# HIL_Header.net
KiCad netlist of a schematic drawn in Altium Designer
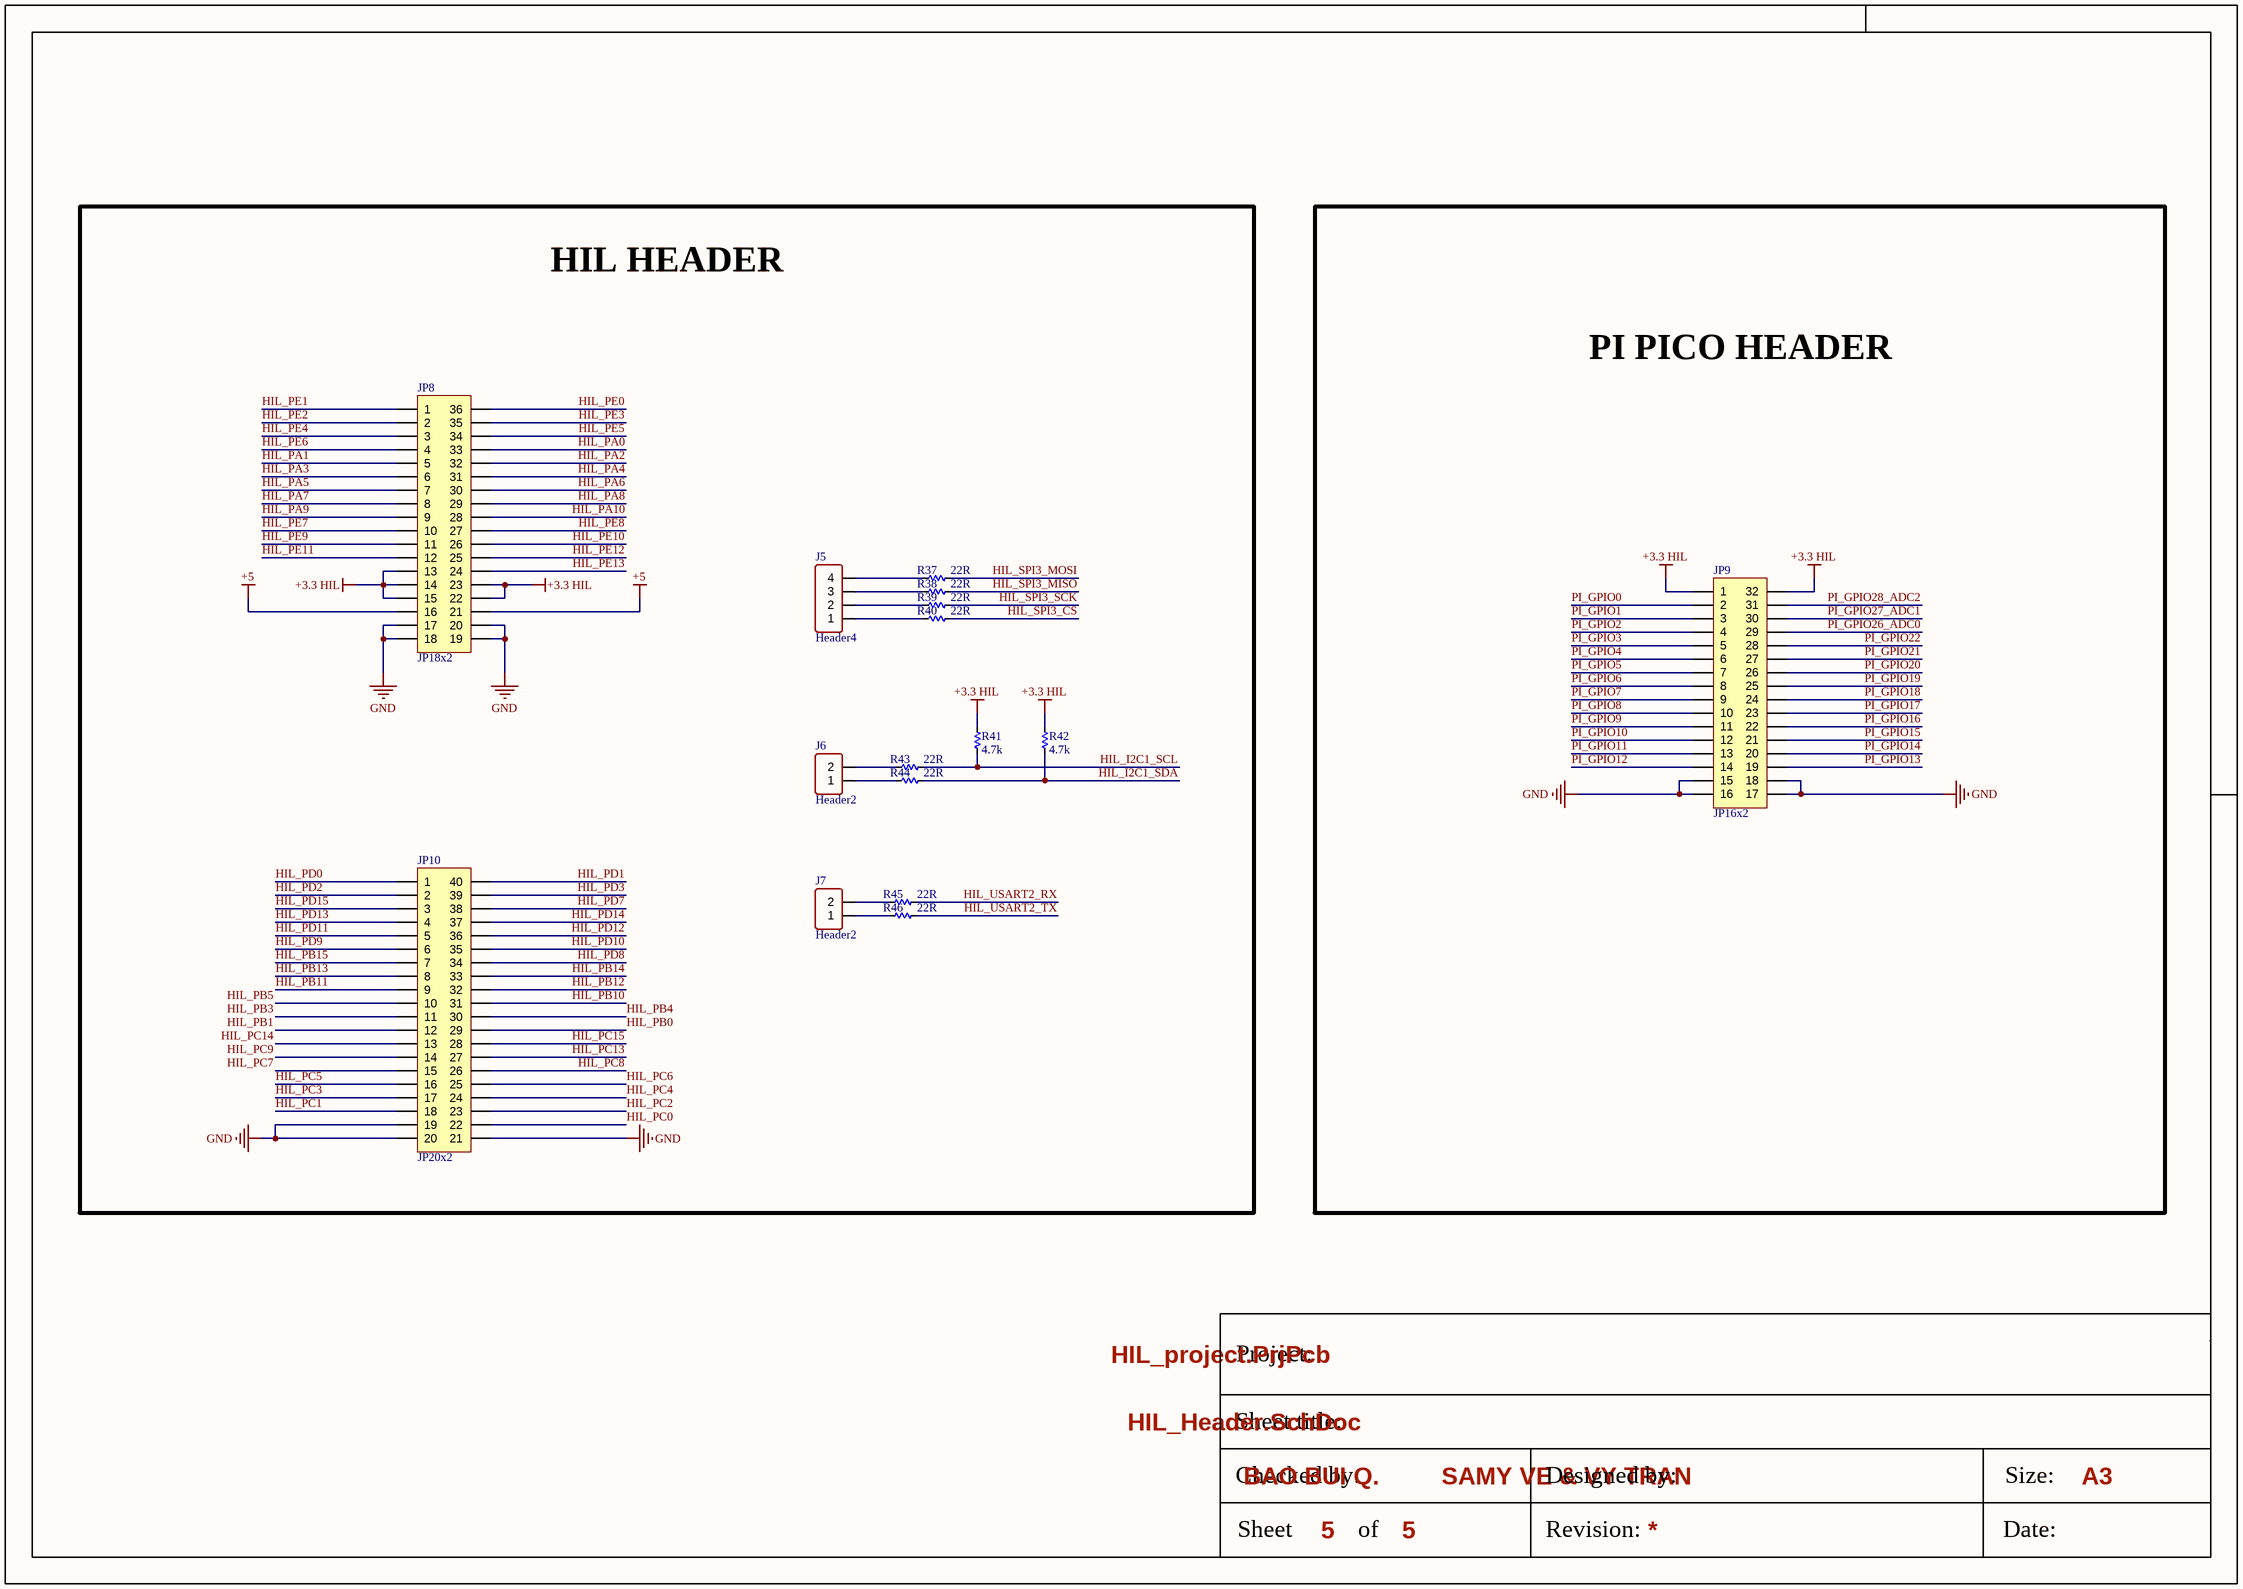
[diagram p0: HIL_Header.SchDoc]

(export (version "E")
  (design (tool "Eeschema 10.0.6"))
  (components
    (comp (ref "J5")
      (value "Header4")
      (footprint "XH2.54-4-DIP")
      (description "Connector 4")
      (fields
        (field (name "MANUFACTURER") "Würth Elektronik eiSos GmbH")
        (field (name "PARTNO") "613002143121")
        (field (name "CREATED BY") "Karrer Zheng")
      )
      (libsource (lib "Library") (part "Header4"))
    )
    (comp (ref "J6")
      (value "Header2")
      (footprint "XH2.54-2-DIP")
      (description "Connector 2")
      (fields
        (field (name "MANUFACTURER") "Würth Elektronik eiSos GmbH")
        (field (name "PARTNO") "613002143121")
        (field (name "CREATED BY") "Karrer Zheng")
      )
      (libsource (lib "Library") (part "Header2"))
    )
    (comp (ref "J7")
      (value "Header2")
      (footprint "XH2.54-2-DIP")
      (description "Connector 2")
      (fields
        (field (name "MANUFACTURER") "Würth Elektronik eiSos GmbH")
        (field (name "PARTNO") "613002143121")
        (field (name "CREATED BY") "Karrer Zheng")
      )
      (libsource (lib "Library") (part "Header2"))
    )
    (comp (ref "JP8")
      (value "JP18x2")
      (footprint "JP18-D2T")
      (description "WR-PHD 2.54 mm Dual Socket Header")
      (fields
        (field (name "MANUFACTURER") "Würth Elektronik eiSos GmbH")
        (field (name "PARTNO") "61303621821")
        (field (name "CREATED BY") "Karrer Zheng")
      )
      (libsource (lib "Library") (part "JP18x2"))
    )
    (comp (ref "JP9")
      (value "JP16x2")
      (footprint "JP16-D2T")
      (description "WR-PHD 2.54 mm Dual Socket Header")
      (fields
        (field (name "MANUFACTURER") "Würth Elektronik eiSos GmbH")
        (field (name "PARTNO") "61303221821")
        (field (name "CREATED BY") "Karrer Zheng")
      )
      (libsource (lib "Library") (part "JP16x2"))
    )
    (comp (ref "JP10")
      (value "JP20x2")
      (footprint "JP20-D2T")
      (description "WR-PHD 2.54 mm Dual Socket Header")
      (fields
        (field (name "MANUFACTURER") "Würth Elektronik eiSos GmbH")
        (field (name "PARTNO") "61304021821")
        (field (name "CREATED BY") "Karrer Zheng")
      )
      (libsource (lib "Library") (part "JP20x2"))
    )
    (comp (ref "R37")
      (value "22R")
      (footprint "RES-SMD-0603")
      (description "Resistor")
      (fields
        (field (name "MANUFACTURER") "Generic Components")
        (field (name "PUBLISHER") "Altium Hobart Technology Centre")
      )
      (libsource (lib "Library") (part "Res-SMD"))
    )
    (comp (ref "R38")
      (value "22R")
      (footprint "RES-SMD-0603")
      (description "Resistor")
      (fields
        (field (name "MANUFACTURER") "Generic Components")
        (field (name "PUBLISHER") "Altium Hobart Technology Centre")
      )
      (libsource (lib "Library") (part "Res-SMD"))
    )
    (comp (ref "R39")
      (value "22R")
      (footprint "RES-SMD-0603")
      (description "Resistor")
      (fields
        (field (name "MANUFACTURER") "Generic Components")
        (field (name "PUBLISHER") "Altium Hobart Technology Centre")
      )
      (libsource (lib "Library") (part "Res-SMD"))
    )
    (comp (ref "R40")
      (value "22R")
      (footprint "RES-SMD-0603")
      (description "Resistor")
      (fields
        (field (name "MANUFACTURER") "Generic Components")
        (field (name "PUBLISHER") "Altium Hobart Technology Centre")
      )
      (libsource (lib "Library") (part "Res-SMD"))
    )
    (comp (ref "R41")
      (value "4.7k")
      (footprint "RES-SMD-0603")
      (description "Resistor")
      (fields
        (field (name "MANUFACTURER") "Generic Components")
        (field (name "PUBLISHER") "Altium Hobart Technology Centre")
      )
      (libsource (lib "Library") (part "Res-SMD"))
    )
    (comp (ref "R42")
      (value "4.7k")
      (footprint "RES-SMD-0603")
      (description "Resistor")
      (fields
        (field (name "MANUFACTURER") "Generic Components")
        (field (name "PUBLISHER") "Altium Hobart Technology Centre")
      )
      (libsource (lib "Library") (part "Res-SMD"))
    )
    (comp (ref "R43")
      (value "22R")
      (footprint "RES-SMD-0603")
      (description "Resistor")
      (fields
        (field (name "MANUFACTURER") "Generic Components")
        (field (name "PUBLISHER") "Altium Hobart Technology Centre")
      )
      (libsource (lib "Library") (part "Res-SMD"))
    )
    (comp (ref "R44")
      (value "22R")
      (footprint "RES-SMD-0603")
      (description "Resistor")
      (fields
        (field (name "MANUFACTURER") "Generic Components")
        (field (name "PUBLISHER") "Altium Hobart Technology Centre")
      )
      (libsource (lib "Library") (part "Res-SMD"))
    )
    (comp (ref "R45")
      (value "22R")
      (footprint "RES-SMD-0603")
      (description "Resistor")
      (fields
        (field (name "MANUFACTURER") "Generic Components")
        (field (name "PUBLISHER") "Altium Hobart Technology Centre")
      )
      (libsource (lib "Library") (part "Res-SMD"))
    )
    (comp (ref "R46")
      (value "22R")
      (footprint "RES-SMD-0603")
      (description "Resistor")
      (fields
        (field (name "MANUFACTURER") "Generic Components")
        (field (name "PUBLISHER") "Altium Hobart Technology Centre")
      )
      (libsource (lib "Library") (part "Res-SMD"))
    )
  )
  (nets
    (net (code "1") (name "+3.3 HIL") (class "Default")
      (node (ref "JP8") (pin "13") (pinfunction "13_13") (pintype "passive"))
      (node (ref "JP8") (pin "14") (pinfunction "14_14") (pintype "passive"))
      (node (ref "JP8") (pin "15") (pinfunction "15_15") (pintype "passive"))
      (node (ref "JP8") (pin "22") (pinfunction "22_22") (pintype "passive"))
      (node (ref "JP8") (pin "23") (pinfunction "23_23") (pintype "passive"))
      (node (ref "JP9") (pin "1") (pinfunction "1_1") (pintype "passive"))
      (node (ref "JP9") (pin "32") (pinfunction "32_32") (pintype "passive"))
      (node (ref "R41") (pin "1") (pinfunction "1_1") (pintype "passive"))
      (node (ref "R42") (pin "1") (pinfunction "1_1") (pintype "passive"))
    )
    (net (code "2") (name "+5") (class "Default")
      (node (ref "JP8") (pin "16") (pinfunction "16_16") (pintype "passive"))
      (node (ref "JP8") (pin "21") (pinfunction "21_21") (pintype "passive"))
    )
    (net (code "3") (name "/HIL_I2C1_SCL") (class "Default")
      (node (ref "R41") (pin "2") (pinfunction "2_2") (pintype "passive"))
      (node (ref "R43") (pin "1") (pinfunction "1_1") (pintype "passive"))
    )
    (net (code "4") (name "/HIL_I2C1_SDA") (class "Default")
      (node (ref "R42") (pin "2") (pinfunction "2_2") (pintype "passive"))
      (node (ref "R44") (pin "1") (pinfunction "1_1") (pintype "passive"))
    )
    (net (code "5") (name "/HIL_PA0") (class "Default")
      (node (ref "JP8") (pin "33") (pinfunction "33_33") (pintype "passive"))
    )
    (net (code "6") (name "/HIL_PA1") (class "Default")
      (node (ref "JP8") (pin "5") (pinfunction "5_5") (pintype "passive"))
    )
    (net (code "7") (name "/HIL_PA2") (class "Default")
      (node (ref "JP8") (pin "32") (pinfunction "32_32") (pintype "passive"))
    )
    (net (code "8") (name "/HIL_PA3") (class "Default")
      (node (ref "JP8") (pin "6") (pinfunction "6_6") (pintype "passive"))
    )
    (net (code "9") (name "/HIL_PA4") (class "Default")
      (node (ref "JP8") (pin "31") (pinfunction "31_31") (pintype "passive"))
    )
    (net (code "10") (name "/HIL_PA5") (class "Default")
      (node (ref "JP8") (pin "7") (pinfunction "7_7") (pintype "passive"))
    )
    (net (code "11") (name "/HIL_PA6") (class "Default")
      (node (ref "JP8") (pin "30") (pinfunction "30_30") (pintype "passive"))
    )
    (net (code "12") (name "/HIL_PA7") (class "Default")
      (node (ref "JP8") (pin "8") (pinfunction "8_8") (pintype "passive"))
    )
    (net (code "13") (name "/HIL_PA8") (class "Default")
      (node (ref "JP8") (pin "29") (pinfunction "29_29") (pintype "passive"))
    )
    (net (code "14") (name "/HIL_PA9") (class "Default")
      (node (ref "JP8") (pin "9") (pinfunction "9_9") (pintype "passive"))
    )
    (net (code "15") (name "/HIL_PA10") (class "Default")
      (node (ref "JP8") (pin "28") (pinfunction "28_28") (pintype "passive"))
    )
    (net (code "16") (name "/HIL_PB0") (class "Default")
      (node (ref "JP10") (pin "29") (pinfunction "29_29") (pintype "passive"))
    )
    (net (code "17") (name "/HIL_PB1") (class "Default")
      (node (ref "JP10") (pin "12") (pinfunction "12_12") (pintype "passive"))
    )
    (net (code "18") (name "/HIL_PB3") (class "Default")
      (node (ref "JP10") (pin "11") (pinfunction "11_11") (pintype "passive"))
    )
    (net (code "19") (name "/HIL_PB4") (class "Default")
      (node (ref "JP10") (pin "30") (pinfunction "30_30") (pintype "passive"))
    )
    (net (code "20") (name "/HIL_PB5") (class "Default")
      (node (ref "JP10") (pin "10") (pinfunction "10_10") (pintype "passive"))
    )
    (net (code "21") (name "/HIL_PB10") (class "Default")
      (node (ref "JP10") (pin "31") (pinfunction "31_31") (pintype "passive"))
    )
    (net (code "22") (name "/HIL_PB11") (class "Default")
      (node (ref "JP10") (pin "9") (pinfunction "9_9") (pintype "passive"))
    )
    (net (code "23") (name "/HIL_PB12") (class "Default")
      (node (ref "JP10") (pin "32") (pinfunction "32_32") (pintype "passive"))
    )
    (net (code "24") (name "/HIL_PB13") (class "Default")
      (node (ref "JP10") (pin "8") (pinfunction "8_8") (pintype "passive"))
    )
    (net (code "25") (name "/HIL_PB14") (class "Default")
      (node (ref "JP10") (pin "33") (pinfunction "33_33") (pintype "passive"))
    )
    (net (code "26") (name "/HIL_PB15") (class "Default")
      (node (ref "JP10") (pin "7") (pinfunction "7_7") (pintype "passive"))
    )
    (net (code "27") (name "/HIL_PC0") (class "Default")
      (node (ref "JP10") (pin "22") (pinfunction "22_22") (pintype "passive"))
    )
    (net (code "28") (name "/HIL_PC1") (class "Default")
      (node (ref "JP10") (pin "18") (pinfunction "18_18") (pintype "passive"))
    )
    (net (code "29") (name "/HIL_PC2") (class "Default")
      (node (ref "JP10") (pin "23") (pinfunction "23_23") (pintype "passive"))
    )
    (net (code "30") (name "/HIL_PC3") (class "Default")
      (node (ref "JP10") (pin "17") (pinfunction "17_17") (pintype "passive"))
    )
    (net (code "31") (name "/HIL_PC4") (class "Default")
      (node (ref "JP10") (pin "24") (pinfunction "24_24") (pintype "passive"))
    )
    (net (code "32") (name "/HIL_PC5") (class "Default")
      (node (ref "JP10") (pin "16") (pinfunction "16_16") (pintype "passive"))
    )
    (net (code "33") (name "/HIL_PC6") (class "Default")
      (node (ref "JP10") (pin "25") (pinfunction "25_25") (pintype "passive"))
    )
    (net (code "34") (name "/HIL_PC7") (class "Default")
      (node (ref "JP10") (pin "15") (pinfunction "15_15") (pintype "passive"))
    )
    (net (code "35") (name "/HIL_PC8") (class "Default")
      (node (ref "JP10") (pin "26") (pinfunction "26_26") (pintype "passive"))
    )
    (net (code "36") (name "/HIL_PC9") (class "Default")
      (node (ref "JP10") (pin "14") (pinfunction "14_14") (pintype "passive"))
    )
    (net (code "37") (name "/HIL_PC13") (class "Default")
      (node (ref "JP10") (pin "27") (pinfunction "27_27") (pintype "passive"))
    )
    (net (code "38") (name "/HIL_PC14") (class "Default")
      (node (ref "JP10") (pin "13") (pinfunction "13_13") (pintype "passive"))
    )
    (net (code "39") (name "/HIL_PC15") (class "Default")
      (node (ref "JP10") (pin "28") (pinfunction "28_28") (pintype "passive"))
    )
    (net (code "40") (name "/HIL_PD0") (class "Default")
      (node (ref "JP10") (pin "1") (pinfunction "1_1") (pintype "passive"))
    )
    (net (code "41") (name "/HIL_PD1") (class "Default")
      (node (ref "JP10") (pin "40") (pinfunction "40_40") (pintype "passive"))
    )
    (net (code "42") (name "/HIL_PD2") (class "Default")
      (node (ref "JP10") (pin "2") (pinfunction "2_2") (pintype "passive"))
    )
    (net (code "43") (name "/HIL_PD3") (class "Default")
      (node (ref "JP10") (pin "39") (pinfunction "39_39") (pintype "passive"))
    )
    (net (code "44") (name "/HIL_PD7") (class "Default")
      (node (ref "JP10") (pin "38") (pinfunction "38_38") (pintype "passive"))
    )
    (net (code "45") (name "/HIL_PD8") (class "Default")
      (node (ref "JP10") (pin "34") (pinfunction "34_34") (pintype "passive"))
    )
    (net (code "46") (name "/HIL_PD9") (class "Default")
      (node (ref "JP10") (pin "6") (pinfunction "6_6") (pintype "passive"))
    )
    (net (code "47") (name "/HIL_PD10") (class "Default")
      (node (ref "JP10") (pin "35") (pinfunction "35_35") (pintype "passive"))
    )
    (net (code "48") (name "/HIL_PD11") (class "Default")
      (node (ref "JP10") (pin "5") (pinfunction "5_5") (pintype "passive"))
    )
    (net (code "49") (name "/HIL_PD12") (class "Default")
      (node (ref "JP10") (pin "36") (pinfunction "36_36") (pintype "passive"))
    )
    (net (code "50") (name "/HIL_PD13") (class "Default")
      (node (ref "JP10") (pin "4") (pinfunction "4_4") (pintype "passive"))
    )
    (net (code "51") (name "/HIL_PD14") (class "Default")
      (node (ref "JP10") (pin "37") (pinfunction "37_37") (pintype "passive"))
    )
    (net (code "52") (name "/HIL_PD15") (class "Default")
      (node (ref "JP10") (pin "3") (pinfunction "3_3") (pintype "passive"))
    )
    (net (code "53") (name "/HIL_PE0") (class "Default")
      (node (ref "JP8") (pin "36") (pinfunction "36_36") (pintype "passive"))
    )
    (net (code "54") (name "/HIL_PE1") (class "Default")
      (node (ref "JP8") (pin "1") (pinfunction "1_1") (pintype "passive"))
    )
    (net (code "55") (name "/HIL_PE2") (class "Default")
      (node (ref "JP8") (pin "2") (pinfunction "2_2") (pintype "passive"))
    )
    (net (code "56") (name "/HIL_PE3") (class "Default")
      (node (ref "JP8") (pin "35") (pinfunction "35_35") (pintype "passive"))
    )
    (net (code "57") (name "/HIL_PE4") (class "Default")
      (node (ref "JP8") (pin "3") (pinfunction "3_3") (pintype "passive"))
    )
    (net (code "58") (name "/HIL_PE5") (class "Default")
      (node (ref "JP8") (pin "34") (pinfunction "34_34") (pintype "passive"))
    )
    (net (code "59") (name "/HIL_PE6") (class "Default")
      (node (ref "JP8") (pin "4") (pinfunction "4_4") (pintype "passive"))
    )
    (net (code "60") (name "/HIL_PE7") (class "Default")
      (node (ref "JP8") (pin "10") (pinfunction "10_10") (pintype "passive"))
    )
    (net (code "61") (name "/HIL_PE8") (class "Default")
      (node (ref "JP8") (pin "27") (pinfunction "27_27") (pintype "passive"))
    )
    (net (code "62") (name "/HIL_PE9") (class "Default")
      (node (ref "JP8") (pin "11") (pinfunction "11_11") (pintype "passive"))
    )
    (net (code "63") (name "/HIL_PE10") (class "Default")
      (node (ref "JP8") (pin "26") (pinfunction "26_26") (pintype "passive"))
    )
    (net (code "64") (name "/HIL_PE11") (class "Default")
      (node (ref "JP8") (pin "12") (pinfunction "12_12") (pintype "passive"))
    )
    (net (code "65") (name "/HIL_PE12") (class "Default")
      (node (ref "JP8") (pin "25") (pinfunction "25_25") (pintype "passive"))
    )
    (net (code "66") (name "/HIL_PE13") (class "Default")
      (node (ref "JP8") (pin "24") (pinfunction "24_24") (pintype "passive"))
    )
    (net (code "67") (name "/HIL_SPI3_CS") (class "Default")
      (node (ref "R40") (pin "1") (pinfunction "1_1") (pintype "passive"))
    )
    (net (code "68") (name "/HIL_SPI3_MISO") (class "Default")
      (node (ref "R38") (pin "1") (pinfunction "1_1") (pintype "passive"))
    )
    (net (code "69") (name "/HIL_SPI3_MOSI") (class "Default")
      (node (ref "R37") (pin "1") (pinfunction "1_1") (pintype "passive"))
    )
    (net (code "70") (name "/HIL_SPI3_SCK") (class "Default")
      (node (ref "R39") (pin "1") (pinfunction "1_1") (pintype "passive"))
    )
    (net (code "71") (name "/HIL_USART2_RX") (class "Default")
      (node (ref "R45") (pin "1") (pinfunction "1_1") (pintype "passive"))
    )
    (net (code "72") (name "/HIL_USART2_TX") (class "Default")
      (node (ref "R46") (pin "1") (pinfunction "1_1") (pintype "passive"))
    )
    (net (code "73") (name "/PI_GPIO0") (class "Default")
      (node (ref "JP9") (pin "2") (pinfunction "2_2") (pintype "passive"))
    )
    (net (code "74") (name "/PI_GPIO1") (class "Default")
      (node (ref "JP9") (pin "3") (pinfunction "3_3") (pintype "passive"))
    )
    (net (code "75") (name "/PI_GPIO2") (class "Default")
      (node (ref "JP9") (pin "4") (pinfunction "4_4") (pintype "passive"))
    )
    (net (code "76") (name "/PI_GPIO3") (class "Default")
      (node (ref "JP9") (pin "5") (pinfunction "5_5") (pintype "passive"))
    )
    (net (code "77") (name "/PI_GPIO4") (class "Default")
      (node (ref "JP9") (pin "6") (pinfunction "6_6") (pintype "passive"))
    )
    (net (code "78") (name "/PI_GPIO5") (class "Default")
      (node (ref "JP9") (pin "7") (pinfunction "7_7") (pintype "passive"))
    )
    (net (code "79") (name "/PI_GPIO6") (class "Default")
      (node (ref "JP9") (pin "8") (pinfunction "8_8") (pintype "passive"))
    )
    (net (code "80") (name "/PI_GPIO7") (class "Default")
      (node (ref "JP9") (pin "9") (pinfunction "9_9") (pintype "passive"))
    )
    (net (code "81") (name "/PI_GPIO8") (class "Default")
      (node (ref "JP9") (pin "10") (pinfunction "10_10") (pintype "passive"))
    )
    (net (code "82") (name "/PI_GPIO9") (class "Default")
      (node (ref "JP9") (pin "11") (pinfunction "11_11") (pintype "passive"))
    )
    (net (code "83") (name "/PI_GPIO10") (class "Default")
      (node (ref "JP9") (pin "12") (pinfunction "12_12") (pintype "passive"))
    )
    (net (code "84") (name "/PI_GPIO11") (class "Default")
      (node (ref "JP9") (pin "13") (pinfunction "13_13") (pintype "passive"))
    )
    (net (code "85") (name "/PI_GPIO12") (class "Default")
      (node (ref "JP9") (pin "14") (pinfunction "14_14") (pintype "passive"))
    )
    (net (code "86") (name "/PI_GPIO13") (class "Default")
      (node (ref "JP9") (pin "19") (pinfunction "19_19") (pintype "passive"))
    )
    (net (code "87") (name "/PI_GPIO14") (class "Default")
      (node (ref "JP9") (pin "20") (pinfunction "20_20") (pintype "passive"))
    )
    (net (code "88") (name "/PI_GPIO15") (class "Default")
      (node (ref "JP9") (pin "21") (pinfunction "21_21") (pintype "passive"))
    )
    (net (code "89") (name "/PI_GPIO16") (class "Default")
      (node (ref "JP9") (pin "22") (pinfunction "22_22") (pintype "passive"))
    )
    (net (code "90") (name "/PI_GPIO17") (class "Default")
      (node (ref "JP9") (pin "23") (pinfunction "23_23") (pintype "passive"))
    )
    (net (code "91") (name "/PI_GPIO18") (class "Default")
      (node (ref "JP9") (pin "24") (pinfunction "24_24") (pintype "passive"))
    )
    (net (code "92") (name "/PI_GPIO19") (class "Default")
      (node (ref "JP9") (pin "25") (pinfunction "25_25") (pintype "passive"))
    )
    (net (code "93") (name "/PI_GPIO20") (class "Default")
      (node (ref "JP9") (pin "26") (pinfunction "26_26") (pintype "passive"))
    )
    (net (code "94") (name "/PI_GPIO21") (class "Default")
      (node (ref "JP9") (pin "27") (pinfunction "27_27") (pintype "passive"))
    )
    (net (code "95") (name "/PI_GPIO22") (class "Default")
      (node (ref "JP9") (pin "28") (pinfunction "28_28") (pintype "passive"))
    )
    (net (code "96") (name "/PI_GPIO26_ADC0") (class "Default")
      (node (ref "JP9") (pin "29") (pinfunction "29_29") (pintype "passive"))
    )
    (net (code "97") (name "/PI_GPIO27_ADC1") (class "Default")
      (node (ref "JP9") (pin "30") (pinfunction "30_30") (pintype "passive"))
    )
    (net (code "98") (name "/PI_GPIO28_ADC2") (class "Default")
      (node (ref "JP9") (pin "31") (pinfunction "31_31") (pintype "passive"))
    )
    (net (code "99") (name "GND") (class "Default")
      (node (ref "JP10") (pin "19") (pinfunction "19_19") (pintype "passive"))
      (node (ref "JP10") (pin "20") (pinfunction "20_20") (pintype "passive"))
      (node (ref "JP10") (pin "21") (pinfunction "21_21") (pintype "passive"))
      (node (ref "JP8") (pin "17") (pinfunction "17_17") (pintype "passive"))
      (node (ref "JP8") (pin "18") (pinfunction "18_18") (pintype "passive"))
      (node (ref "JP8") (pin "19") (pinfunction "19_19") (pintype "passive"))
      (node (ref "JP8") (pin "20") (pinfunction "20_20") (pintype "passive"))
      (node (ref "JP9") (pin "15") (pinfunction "15_15") (pintype "passive"))
      (node (ref "JP9") (pin "16") (pinfunction "16_16") (pintype "passive"))
      (node (ref "JP9") (pin "17") (pinfunction "17_17") (pintype "passive"))
      (node (ref "JP9") (pin "18") (pinfunction "18_18") (pintype "passive"))
    )
    (net (code "100") (name "Net-(J5-Pad1)") (class "Default")
      (node (ref "J5") (pin "1") (pinfunction "1_1") (pintype "passive"))
      (node (ref "R40") (pin "2") (pinfunction "2_2") (pintype "passive"))
    )
    (net (code "101") (name "Net-(J5-Pad2)") (class "Default")
      (node (ref "J5") (pin "2") (pinfunction "2_2") (pintype "passive"))
      (node (ref "R39") (pin "2") (pinfunction "2_2") (pintype "passive"))
    )
    (net (code "102") (name "Net-(J5-Pad3)") (class "Default")
      (node (ref "J5") (pin "3") (pinfunction "3_3") (pintype "passive"))
      (node (ref "R38") (pin "2") (pinfunction "2_2") (pintype "passive"))
    )
    (net (code "103") (name "Net-(J5-Pad4)") (class "Default")
      (node (ref "J5") (pin "4") (pinfunction "4_4") (pintype "passive"))
      (node (ref "R37") (pin "2") (pinfunction "2_2") (pintype "passive"))
    )
    (net (code "104") (name "Net-(J6-Pad1)") (class "Default")
      (node (ref "J6") (pin "1") (pinfunction "1_1") (pintype "passive"))
      (node (ref "R44") (pin "2") (pinfunction "2_2") (pintype "passive"))
    )
    (net (code "105") (name "Net-(J6-Pad2)") (class "Default")
      (node (ref "J6") (pin "2") (pinfunction "2_2") (pintype "passive"))
      (node (ref "R43") (pin "2") (pinfunction "2_2") (pintype "passive"))
    )
    (net (code "106") (name "Net-(J7-Pad1)") (class "Default")
      (node (ref "J7") (pin "1") (pinfunction "1_1") (pintype "passive"))
      (node (ref "R46") (pin "2") (pinfunction "2_2") (pintype "passive"))
    )
    (net (code "107") (name "Net-(J7-Pad2)") (class "Default")
      (node (ref "J7") (pin "2") (pinfunction "2_2") (pintype "passive"))
      (node (ref "R45") (pin "2") (pinfunction "2_2") (pintype "passive"))
    )
  )
)
